# A1_PROM_schematic_64_128.net
KiCad netlist of a schematic drawn in EasyEDA
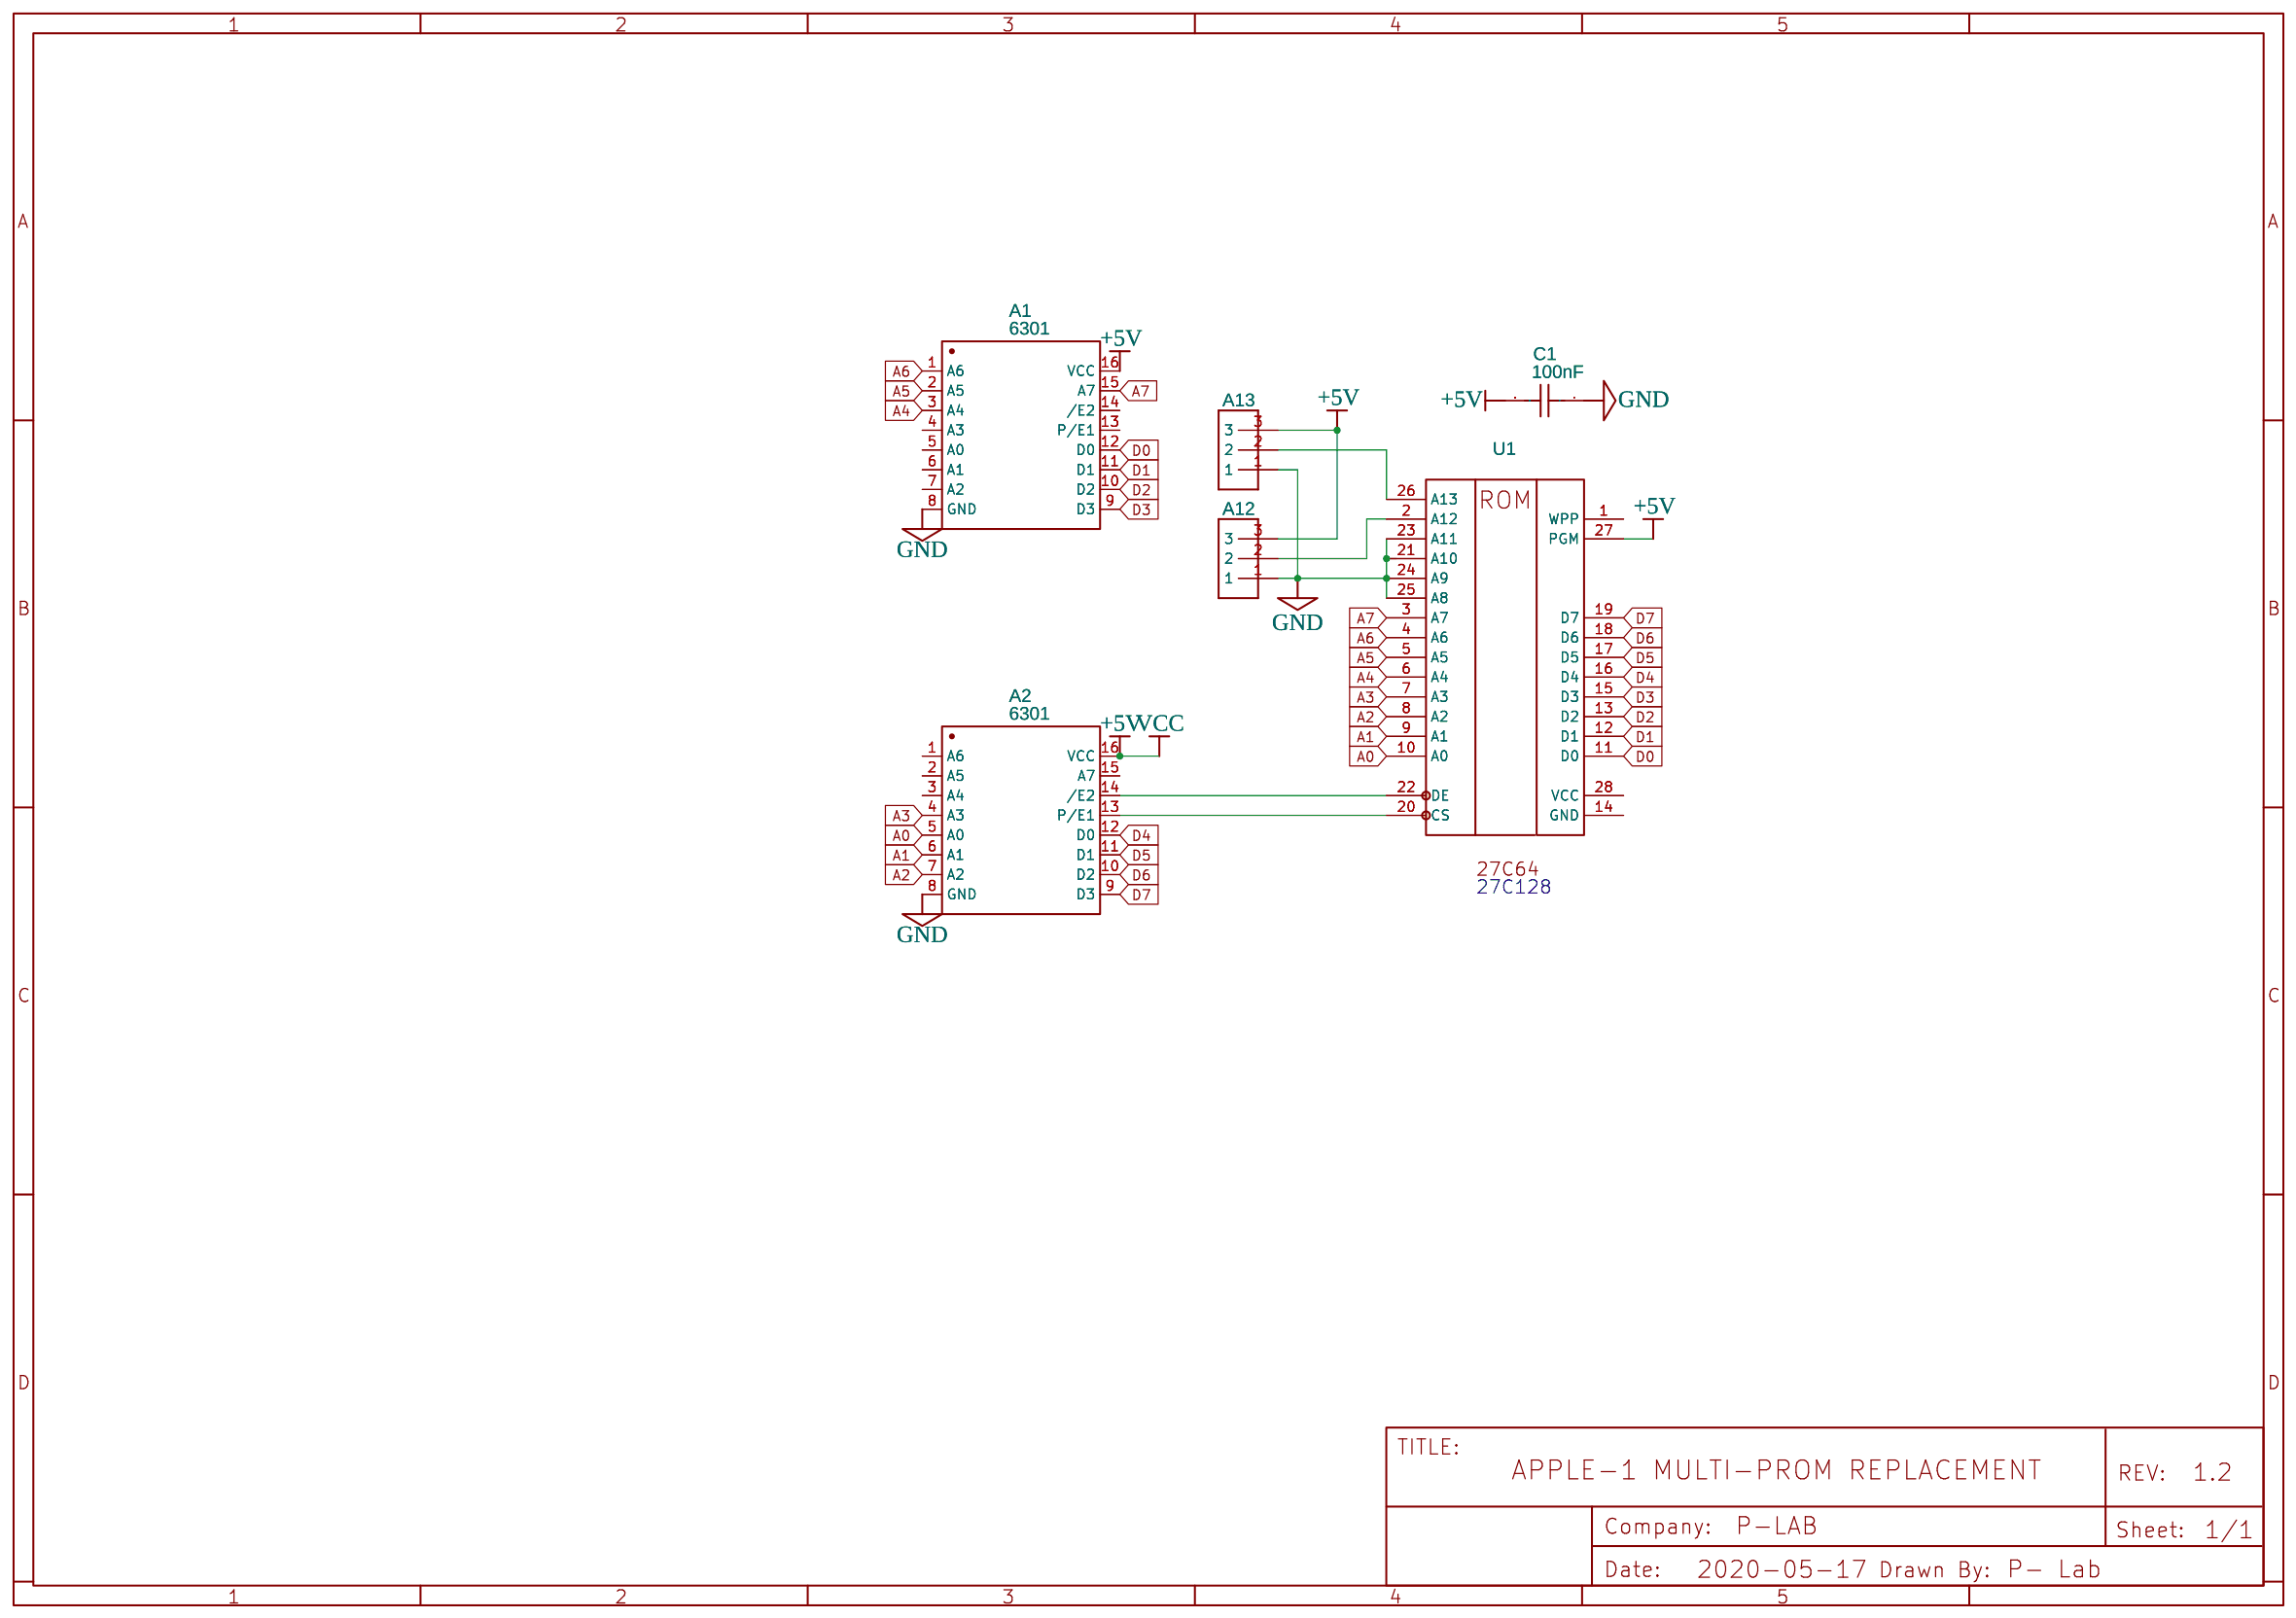
[diagram p0: schematic sheet]

(export (version "E")
  (design (tool "Eeschema 10.0.6"))
  (components
    (comp (ref "A1")
      (value "6301")
      (fields
        (field (name "BOM_Manufacturer Part") "UT232AG-D16-T")
        (field (name "BOM_Supplier Part") "C98142")
      )
      (libsource (lib "") (part "DIP-16"))
    )
    (comp (ref "A2")
      (value "6301")
      (fields
        (field (name "BOM_Manufacturer Part") "UT232AG-D16-T")
        (field (name "BOM_Supplier Part") "C98142")
      )
      (libsource (lib "") (part "DIP-16"))
    )
    (comp (ref "A12") (value "HEADERDIP3HEADERDIP3") (libsource (lib "") (part "HEADERDIP3HEADERDIP3")))
    (comp (ref "A13") (value "HEADERDIP3HEADERDIP3") (libsource (lib "") (part "HEADERDIP3HEADERDIP3")))
    (comp (ref "C1")
      (value "100nF")
      (fields
        (field (name "BOM_Manufacturer Part") "CT4G-0805-2X1-50V-0.1uF-K")
        (field (name "BOM_Supplier Part") "C141981")
      )
      (libsource (lib "") (part "CT4G-0805-2X1-50V-0.1UF-K"))
    )
    (comp (ref "U1") (value "27C64") (libsource (lib "") (part "27C128")))
  )
  (nets
    (net (code "1") (name "+5V") (class "Default")
      (node (ref "A1") (pin "16") (pinfunction "VCC_16") (pintype "unspecified"))
      (node (ref "A12") (pin "3") (pinfunction "3_3") (pintype "unspecified"))
      (node (ref "A13") (pin "3") (pinfunction "3_3") (pintype "unspecified"))
      (node (ref "A2") (pin "16") (pinfunction "VCC_16") (pintype "unspecified"))
      (node (ref "C1") (pin "2") (pinfunction "2_2") (pintype "unspecified"))
      (node (ref "U1") (pin "27") (pinfunction "PGM_27") (pintype "unspecified"))
    )
    (net (code "2") (name "A0") (class "Default")
      (node (ref "A2") (pin "5") (pinfunction "A0_5") (pintype "unspecified"))
      (node (ref "U1") (pin "10") (pinfunction "A0_10") (pintype "unspecified"))
    )
    (net (code "3") (name "A1") (class "Default")
      (node (ref "A2") (pin "6") (pinfunction "A1_6") (pintype "unspecified"))
      (node (ref "U1") (pin "9") (pinfunction "A1_9") (pintype "unspecified"))
    )
    (net (code "4") (name "A2") (class "Default")
      (node (ref "A2") (pin "7") (pinfunction "A2_7") (pintype "unspecified"))
      (node (ref "U1") (pin "8") (pinfunction "A2_8") (pintype "unspecified"))
    )
    (net (code "5") (name "A3") (class "Default")
      (node (ref "A2") (pin "4") (pinfunction "A3_4") (pintype "unspecified"))
      (node (ref "U1") (pin "7") (pinfunction "A3_7") (pintype "unspecified"))
    )
    (net (code "6") (name "A4") (class "Default")
      (node (ref "A1") (pin "3") (pinfunction "A4_3") (pintype "unspecified"))
      (node (ref "U1") (pin "6") (pinfunction "A4_6") (pintype "unspecified"))
    )
    (net (code "7") (name "A5") (class "Default")
      (node (ref "A1") (pin "2") (pinfunction "A5_2") (pintype "unspecified"))
      (node (ref "U1") (pin "5") (pinfunction "A5_5") (pintype "unspecified"))
    )
    (net (code "8") (name "A6") (class "Default")
      (node (ref "A1") (pin "1") (pinfunction "A6_1") (pintype "unspecified"))
      (node (ref "U1") (pin "4") (pinfunction "A6_4") (pintype "unspecified"))
    )
    (net (code "9") (name "A7") (class "Default")
      (node (ref "A1") (pin "15") (pinfunction "A7_15") (pintype "unspecified"))
      (node (ref "U1") (pin "3") (pinfunction "A7_3") (pintype "unspecified"))
    )
    (net (code "10") (name "D0") (class "Default")
      (node (ref "A1") (pin "12") (pinfunction "D0_12") (pintype "unspecified"))
      (node (ref "U1") (pin "11") (pinfunction "D0_11") (pintype "unspecified"))
    )
    (net (code "11") (name "D1") (class "Default")
      (node (ref "A1") (pin "11") (pinfunction "D1_11") (pintype "unspecified"))
      (node (ref "U1") (pin "12") (pinfunction "D1_12") (pintype "unspecified"))
    )
    (net (code "12") (name "D2") (class "Default")
      (node (ref "A1") (pin "10") (pinfunction "D2_10") (pintype "unspecified"))
      (node (ref "U1") (pin "13") (pinfunction "D2_13") (pintype "unspecified"))
    )
    (net (code "13") (name "D3") (class "Default")
      (node (ref "A1") (pin "9") (pinfunction "D3_9") (pintype "unspecified"))
      (node (ref "U1") (pin "15") (pinfunction "D3_15") (pintype "unspecified"))
    )
    (net (code "14") (name "D4") (class "Default")
      (node (ref "A2") (pin "12") (pinfunction "D0_12") (pintype "unspecified"))
      (node (ref "U1") (pin "16") (pinfunction "D4_16") (pintype "unspecified"))
    )
    (net (code "15") (name "D5") (class "Default")
      (node (ref "A2") (pin "11") (pinfunction "D1_11") (pintype "unspecified"))
      (node (ref "U1") (pin "17") (pinfunction "D5_17") (pintype "unspecified"))
    )
    (net (code "16") (name "D6") (class "Default")
      (node (ref "A2") (pin "10") (pinfunction "D2_10") (pintype "unspecified"))
      (node (ref "U1") (pin "18") (pinfunction "D6_18") (pintype "unspecified"))
    )
    (net (code "17") (name "D7") (class "Default")
      (node (ref "A2") (pin "9") (pinfunction "D3_9") (pintype "unspecified"))
      (node (ref "U1") (pin "19") (pinfunction "D7_19") (pintype "unspecified"))
    )
    (net (code "18") (name "GND") (class "Default")
      (node (ref "A1") (pin "8") (pinfunction "GND_8") (pintype "unspecified"))
      (node (ref "A12") (pin "1") (pinfunction "1_1") (pintype "unspecified"))
      (node (ref "A13") (pin "1") (pinfunction "1_1") (pintype "unspecified"))
      (node (ref "A2") (pin "8") (pinfunction "GND_8") (pintype "unspecified"))
      (node (ref "C1") (pin "1") (pinfunction "1_1") (pintype "unspecified"))
      (node (ref "U1") (pin "21") (pinfunction "A10_21") (pintype "unspecified"))
      (node (ref "U1") (pin "23") (pinfunction "A11_23") (pintype "unspecified"))
      (node (ref "U1") (pin "24") (pinfunction "A9_24") (pintype "unspecified"))
      (node (ref "U1") (pin "25") (pinfunction "A8_25") (pintype "unspecified"))
    )
    (net (code "19") (name "Net-(A2-P{slash}E1)") (class "Default")
      (node (ref "A2") (pin "13") (pinfunction "P/E1_13") (pintype "unspecified"))
      (node (ref "U1") (pin "20") (pinfunction "CS_20") (pintype "unspecified"))
    )
    (net (code "20") (name "Net-(A2-{slash}E2)") (class "Default")
      (node (ref "A2") (pin "14") (pinfunction "/E2_14") (pintype "unspecified"))
      (node (ref "U1") (pin "22") (pinfunction "DE_22") (pintype "unspecified"))
    )
    (net (code "21") (name "Net-(U1-A12)") (class "Default")
      (node (ref "A12") (pin "2") (pinfunction "2_2") (pintype "unspecified"))
      (node (ref "U1") (pin "2") (pinfunction "A12_2") (pintype "unspecified"))
    )
    (net (code "22") (name "Net-(U1-A13)") (class "Default")
      (node (ref "A13") (pin "2") (pinfunction "2_2") (pintype "unspecified"))
      (node (ref "U1") (pin "26") (pinfunction "A13_26") (pintype "unspecified"))
    )
    (net (code "23") (name "unconnected-(A1-A0-Pad5)") (class "Default")
      (node (ref "A1") (pin "5") (pinfunction "A0_5") (pintype "unspecified"))
    )
    (net (code "24") (name "unconnected-(A1-A1-Pad6)") (class "Default")
      (node (ref "A1") (pin "6") (pinfunction "A1_6") (pintype "unspecified"))
    )
    (net (code "25") (name "unconnected-(A1-A2-Pad7)") (class "Default")
      (node (ref "A1") (pin "7") (pinfunction "A2_7") (pintype "unspecified"))
    )
    (net (code "26") (name "unconnected-(A1-A3-Pad4)") (class "Default")
      (node (ref "A1") (pin "4") (pinfunction "A3_4") (pintype "unspecified"))
    )
    (net (code "27") (name "unconnected-(A1-P{slash}E1-Pad13)") (class "Default")
      (node (ref "A1") (pin "13") (pinfunction "P/E1_13") (pintype "unspecified"))
    )
    (net (code "28") (name "unconnected-(A1-{slash}E2-Pad14)") (class "Default")
      (node (ref "A1") (pin "14") (pinfunction "/E2_14") (pintype "unspecified"))
    )
    (net (code "29") (name "unconnected-(A2-A4-Pad3)") (class "Default")
      (node (ref "A2") (pin "3") (pinfunction "A4_3") (pintype "unspecified"))
    )
    (net (code "30") (name "unconnected-(A2-A5-Pad2)") (class "Default")
      (node (ref "A2") (pin "2") (pinfunction "A5_2") (pintype "unspecified"))
    )
    (net (code "31") (name "unconnected-(A2-A6-Pad1)") (class "Default")
      (node (ref "A2") (pin "1") (pinfunction "A6_1") (pintype "unspecified"))
    )
    (net (code "32") (name "unconnected-(A2-A7-Pad15)") (class "Default")
      (node (ref "A2") (pin "15") (pinfunction "A7_15") (pintype "unspecified"))
    )
    (net (code "33") (name "unconnected-(U1-GND-Pad14)") (class "Default")
      (node (ref "U1") (pin "14") (pinfunction "GND_14") (pintype "unspecified"))
    )
    (net (code "34") (name "unconnected-(U1-VCC-Pad28)") (class "Default")
      (node (ref "U1") (pin "28") (pinfunction "VCC_28") (pintype "unspecified"))
    )
    (net (code "35") (name "unconnected-(U1-WPP-Pad1)") (class "Default")
      (node (ref "U1") (pin "1") (pinfunction "WPP_1") (pintype "unspecified"))
    )
  )
)
